# slave-connector.net
KiCad netlist of a schematic drawn in Altium Designer
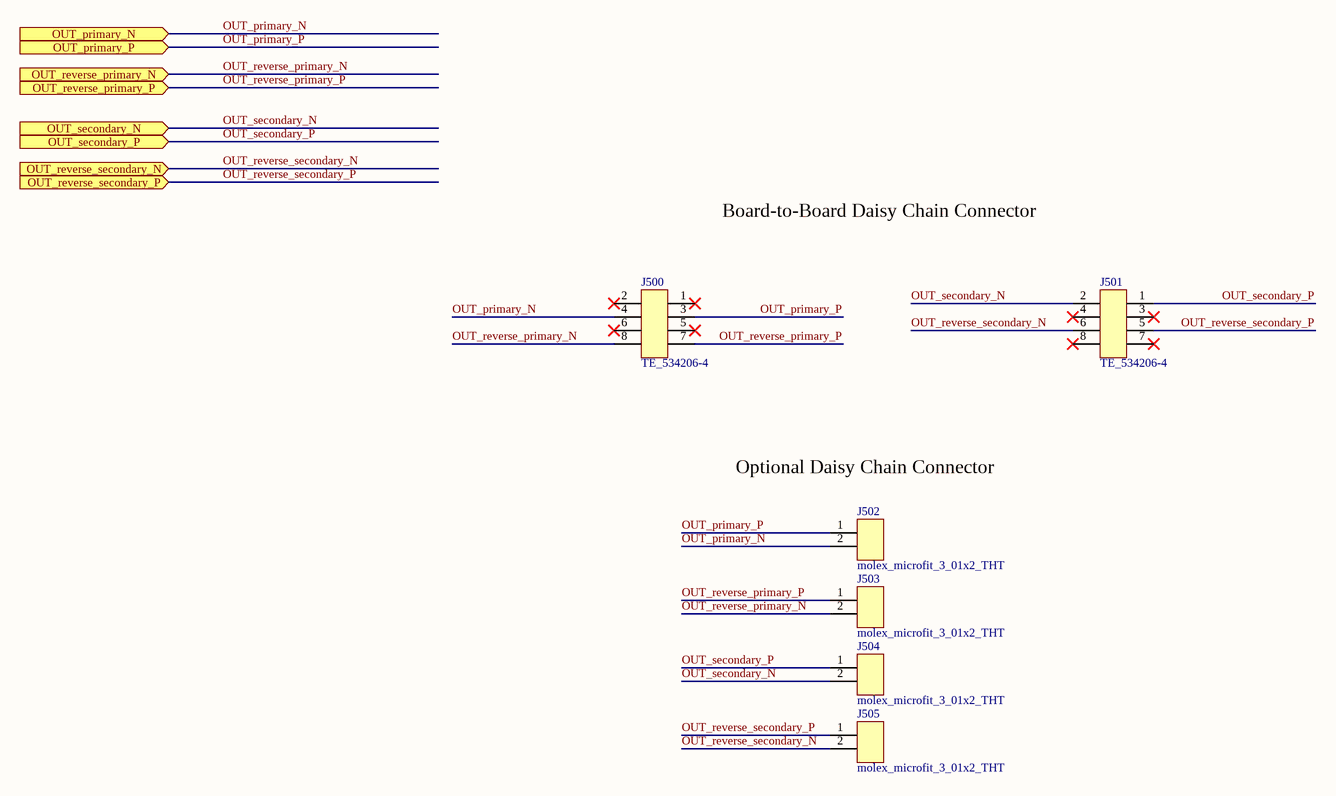
[diagram p0: slave-connector.SchDoc]

(export (version "E")
  (design (tool "Eeschema 10.0.6"))
  (components
    (comp (ref "J500")
      (value "TE_534206-4")
      (footprint "TE_534206-4")
      (description "Board-To-Board Connector, Dual, 2.54 mm, 8 Contacts, Receptacle, Through Hole, 2 Rows")
      (fields (field (name "MANUFACTURER") "TE"))
      (libsource (lib "OE750") (part "X2x4"))
    )
    (comp (ref "J501")
      (value "TE_534206-4")
      (footprint "TE_534206-4")
      (description "Board-To-Board Connector, Dual, 2.54 mm, 8 Contacts, Receptacle, Through Hole, 2 Rows")
      (fields (field (name "MANUFACTURER") "TE"))
      (libsource (lib "OE750") (part "X2x4"))
    )
    (comp (ref "J502")
      (value "molex_microfit_3_01x2_THT")
      (footprint "MOLEX_MICROFIT_01x2_THT")
      (fields (field (name "MANUFACTURER") "Molex"))
      (libsource (lib "OE750") (part "X2"))
    )
    (comp (ref "J503")
      (value "molex_microfit_3_01x2_THT")
      (footprint "MOLEX_MICROFIT_01x2_THT")
      (fields (field (name "MANUFACTURER") "Molex"))
      (libsource (lib "OE750") (part "X2"))
    )
    (comp (ref "J504")
      (value "molex_microfit_3_01x2_THT")
      (footprint "MOLEX_MICROFIT_01x2_THT")
      (fields (field (name "MANUFACTURER") "Molex"))
      (libsource (lib "OE750") (part "X2"))
    )
    (comp (ref "J505")
      (value "molex_microfit_3_01x2_THT")
      (footprint "MOLEX_MICROFIT_01x2_THT")
      (fields (field (name "MANUFACTURER") "Molex"))
      (libsource (lib "OE750") (part "X2"))
    )
  )
  (nets
    (net (code "1") (name "/OUT_primary_N") (class "Default")
      (node (ref "J500") (pin "4") (pintype "passive"))
      (node (ref "J502") (pin "2") (pintype "passive"))
    )
    (net (code "2") (name "/OUT_primary_P") (class "Default")
      (node (ref "J500") (pin "3") (pintype "passive"))
      (node (ref "J502") (pin "1") (pintype "passive"))
    )
    (net (code "3") (name "/OUT_reverse_primary_N") (class "Default")
      (node (ref "J500") (pin "8") (pintype "passive"))
      (node (ref "J503") (pin "2") (pintype "passive"))
    )
    (net (code "4") (name "/OUT_reverse_primary_P") (class "Default")
      (node (ref "J500") (pin "7") (pintype "passive"))
      (node (ref "J503") (pin "1") (pintype "passive"))
    )
    (net (code "5") (name "/OUT_reverse_secondary_N") (class "Default")
      (node (ref "J501") (pin "6") (pintype "passive"))
      (node (ref "J505") (pin "2") (pintype "passive"))
    )
    (net (code "6") (name "/OUT_reverse_secondary_P") (class "Default")
      (node (ref "J501") (pin "5") (pintype "passive"))
      (node (ref "J505") (pin "1") (pintype "passive"))
    )
    (net (code "7") (name "/OUT_secondary_N") (class "Default")
      (node (ref "J501") (pin "2") (pintype "passive"))
      (node (ref "J504") (pin "2") (pintype "passive"))
    )
    (net (code "8") (name "/OUT_secondary_P") (class "Default")
      (node (ref "J501") (pin "1") (pintype "passive"))
      (node (ref "J504") (pin "1") (pintype "passive"))
    )
    (net (code "9") (name "unconnected-(J500-Pad1)") (class "Default")
      (node (ref "J500") (pin "1") (pintype "passive+no_connect"))
    )
    (net (code "10") (name "unconnected-(J500-Pad2)") (class "Default")
      (node (ref "J500") (pin "2") (pintype "passive+no_connect"))
    )
    (net (code "11") (name "unconnected-(J500-Pad5)") (class "Default")
      (node (ref "J500") (pin "5") (pintype "passive+no_connect"))
    )
    (net (code "12") (name "unconnected-(J500-Pad6)") (class "Default")
      (node (ref "J500") (pin "6") (pintype "passive+no_connect"))
    )
    (net (code "13") (name "unconnected-(J501-Pad3)") (class "Default")
      (node (ref "J501") (pin "3") (pintype "passive+no_connect"))
    )
    (net (code "14") (name "unconnected-(J501-Pad4)") (class "Default")
      (node (ref "J501") (pin "4") (pintype "passive+no_connect"))
    )
    (net (code "15") (name "unconnected-(J501-Pad7)") (class "Default")
      (node (ref "J501") (pin "7") (pintype "passive+no_connect"))
    )
    (net (code "16") (name "unconnected-(J501-Pad8)") (class "Default")
      (node (ref "J501") (pin "8") (pintype "passive+no_connect"))
    )
  )
)
